# SCH_Balun-_SMD_-ENCLOSURE__2026-03-13.net
KiCad netlist of a schematic drawn in EasyEDA
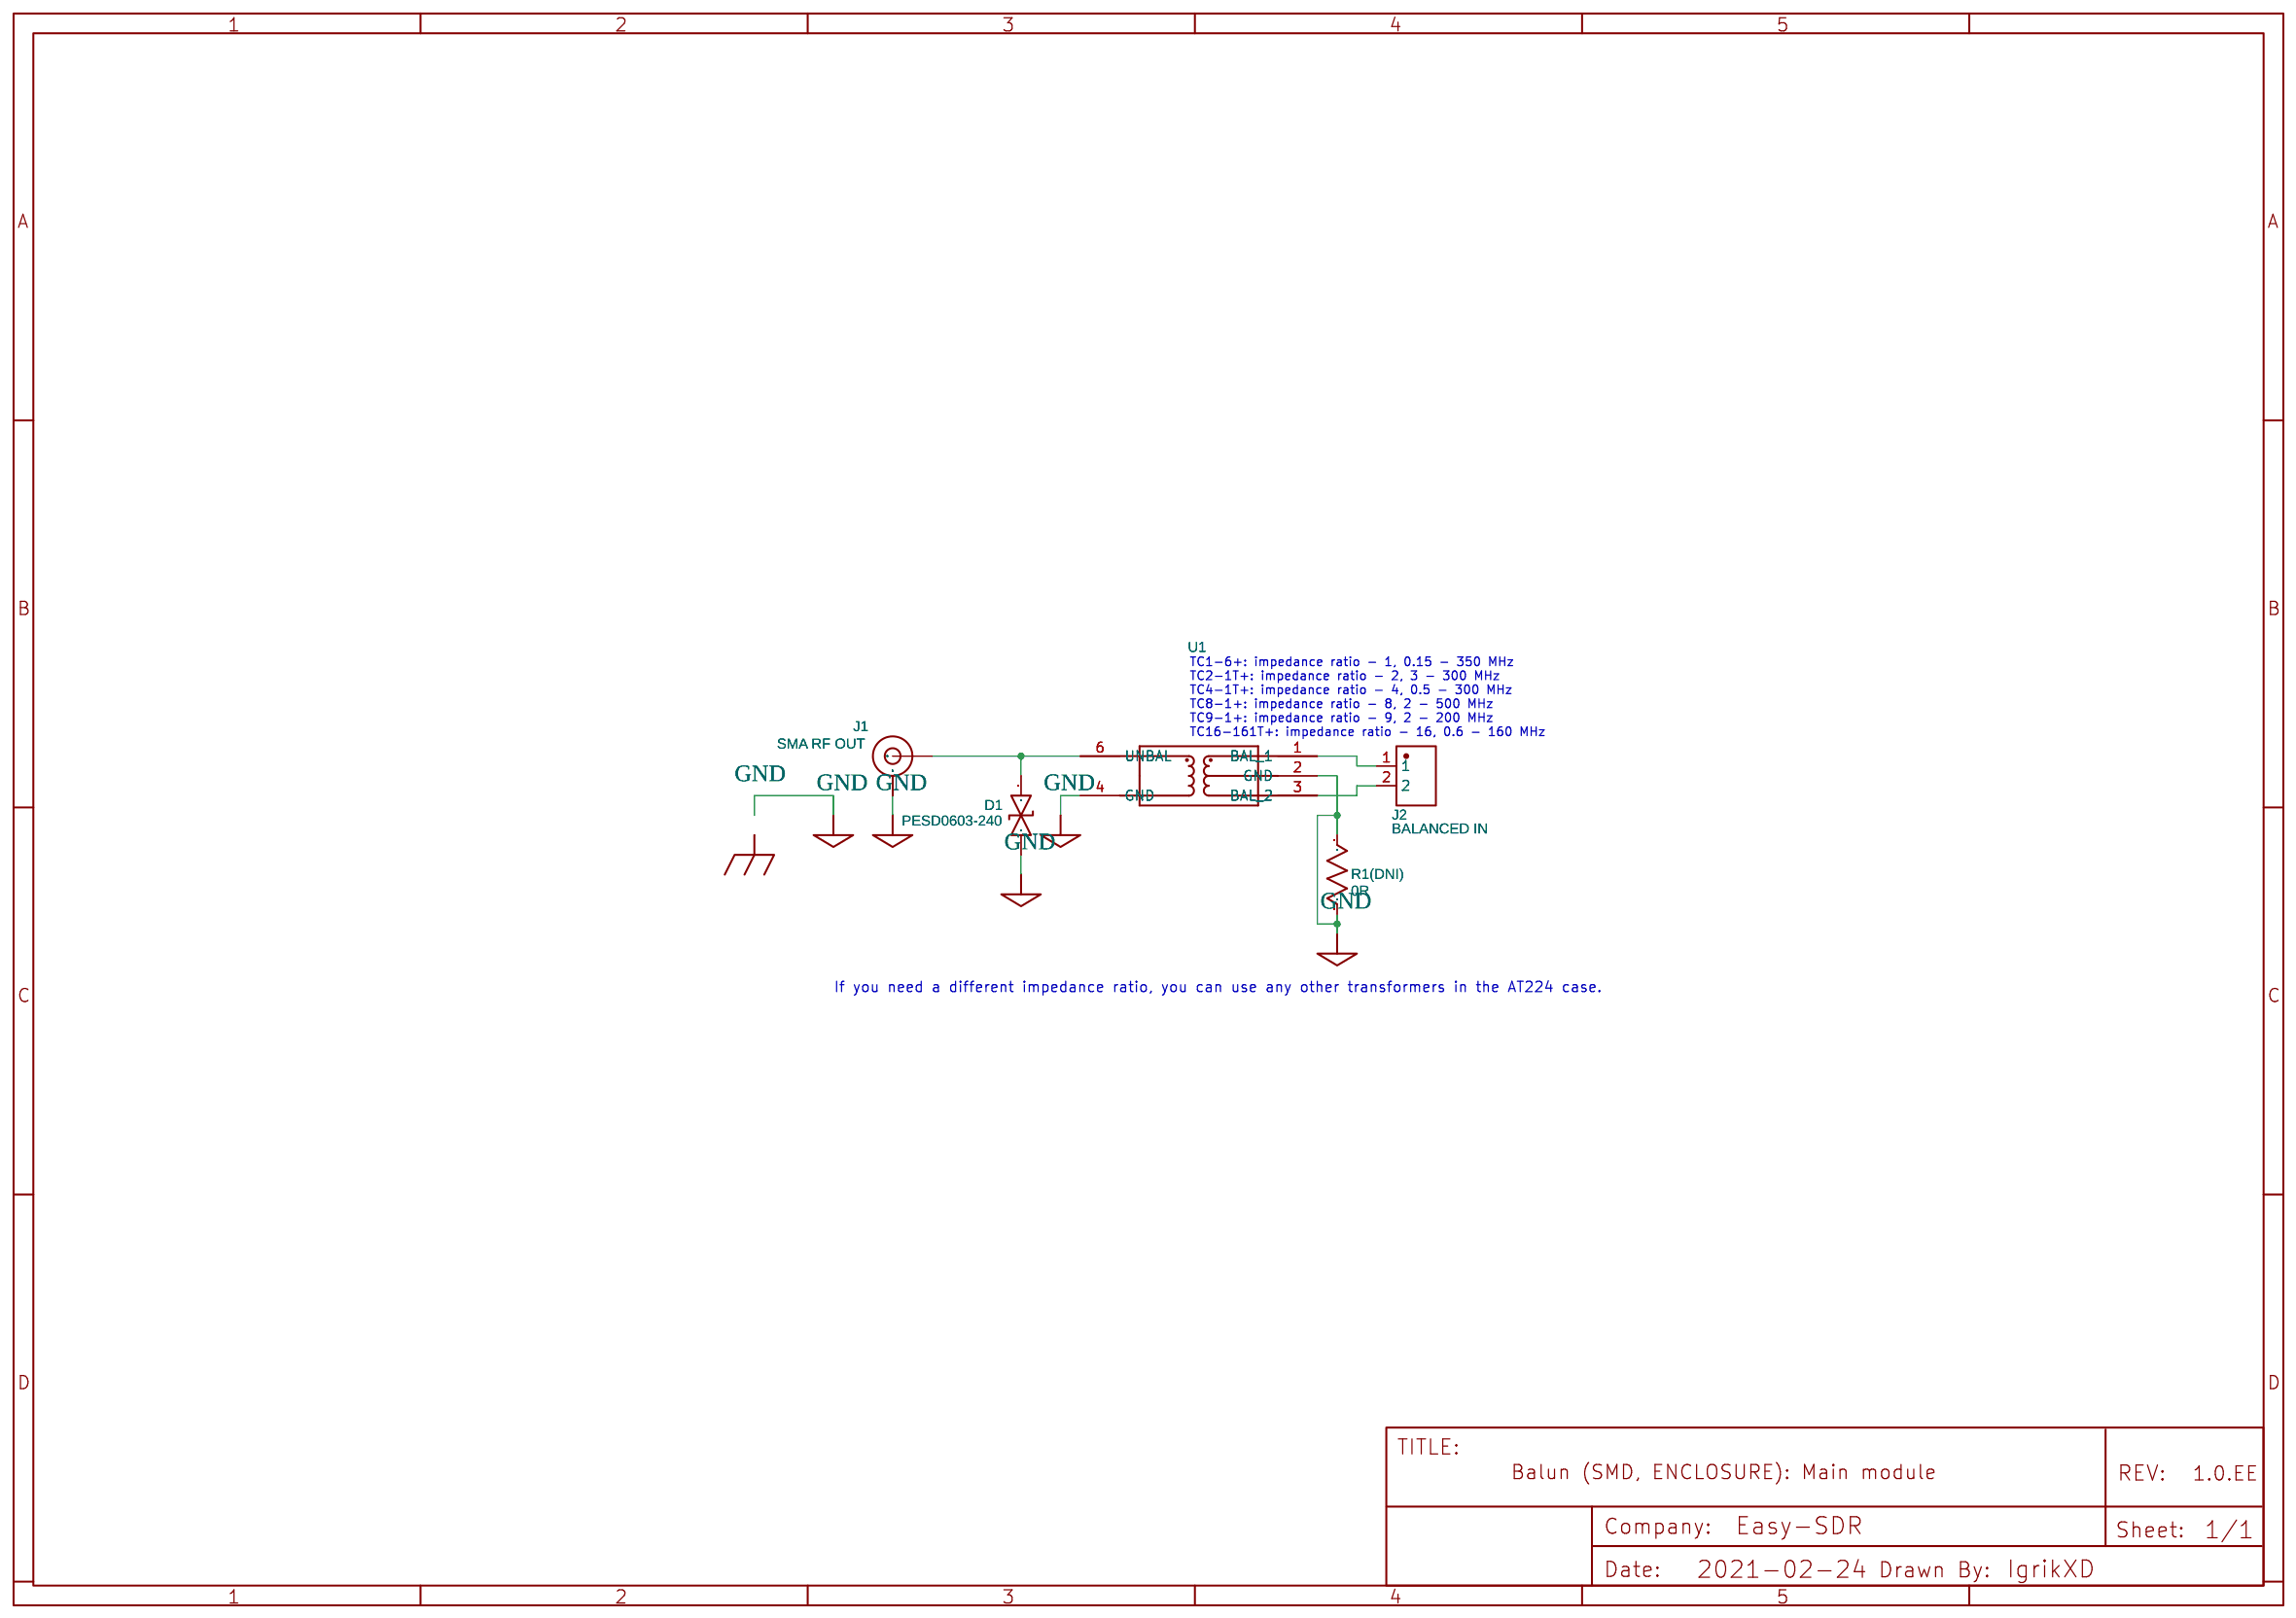
[diagram p0: schematic sheet]

(export (version "E")
  (design (tool "Eeschema 10.0.6"))
  (components
    (comp (ref "D1")
      (value "PESD0603-240")
      (fields (field (name "Manufacturer") "TE Connectivity"))
      (libsource (lib "") (part "PESD0603-240"))
    )
    (comp (ref "J1")
      (value "SMA RF OUT")
      (fields
        (field (name "Manufacturer Part") "KH-SMA-KWE17-G")
        (field (name "Manufacturer") "Shenzhen Kinghelm Elec")
      )
      (libsource (lib "") (part "Unknown_450_-410"))
    )
    (comp (ref "J2")
      (value "BALANCED IN")
      (fields
        (field (name "Manufacturer Part") "XY2500R-D-5.08-2P")
        (field (name "Manufacturer") "Ningbo Xinlaiya Elec.")
      )
      (libsource (lib "") (part "XY2500R-D-5.08-2P"))
    )
    (comp (ref "R1(DNI)")
      (value "0R")
      (fields (field (name "Manufacturer Part") "RTT051000FTP") (field (name "Manufacturer") "RALEC"))
      (libsource (lib "") (part "Resistor"))
    )
    (comp (ref "U1")
      (value "TC9-1+")
      (fields (field (name "Manufacturer") "Mini-Circuits"))
      (libsource (lib "") (part "TC9-1+"))
    )
  )
  (nets
    (net (code "1") (name "GND") (class "Default")
      (node (ref "D1") (pin "1") (pinfunction "1_1") (pintype "unspecified"))
      (node (ref "J1") (pin "1") (pinfunction "GND_1") (pintype "unspecified"))
      (node (ref "J1") (pin "2") (pinfunction "GND_2") (pintype "unspecified"))
      (node (ref "J1") (pin "3") (pinfunction "GND_3") (pintype "unspecified"))
      (node (ref "J1") (pin "4") (pinfunction "GND_4") (pintype "unspecified"))
      (node (ref "R1(DNI)") (pin "1") (pinfunction "1_1") (pintype "unspecified"))
      (node (ref "R1(DNI)") (pin "2") (pinfunction "2_2") (pintype "unspecified"))
      (node (ref "U1") (pin "2") (pinfunction "GND_2") (pintype "unspecified"))
      (node (ref "U1") (pin "4") (pinfunction "GND_4") (pintype "unspecified"))
    )
    (net (code "2") (name "Net-(J1-SIGNAL)") (class "Default")
      (node (ref "D1") (pin "2") (pinfunction "2_2") (pintype "unspecified"))
      (node (ref "J1") (pin "5") (pinfunction "SIGNAL_5") (pintype "unspecified"))
      (node (ref "U1") (pin "6") (pinfunction "UNBAL_6") (pintype "unspecified"))
    )
    (net (code "3") (name "Net-(U1-BAL_1)") (class "Default")
      (node (ref "J2") (pin "1") (pinfunction "1_1") (pintype "unspecified"))
      (node (ref "U1") (pin "1") (pinfunction "BAL_1_1") (pintype "unspecified"))
    )
    (net (code "4") (name "Net-(U1-BAL_2)") (class "Default")
      (node (ref "J2") (pin "2") (pinfunction "2_2") (pintype "unspecified"))
      (node (ref "U1") (pin "3") (pinfunction "BAL_2_3") (pintype "unspecified"))
    )
  )
)
